# Helepolis_Level0.net
KiCad netlist of a schematic drawn in EAGLE
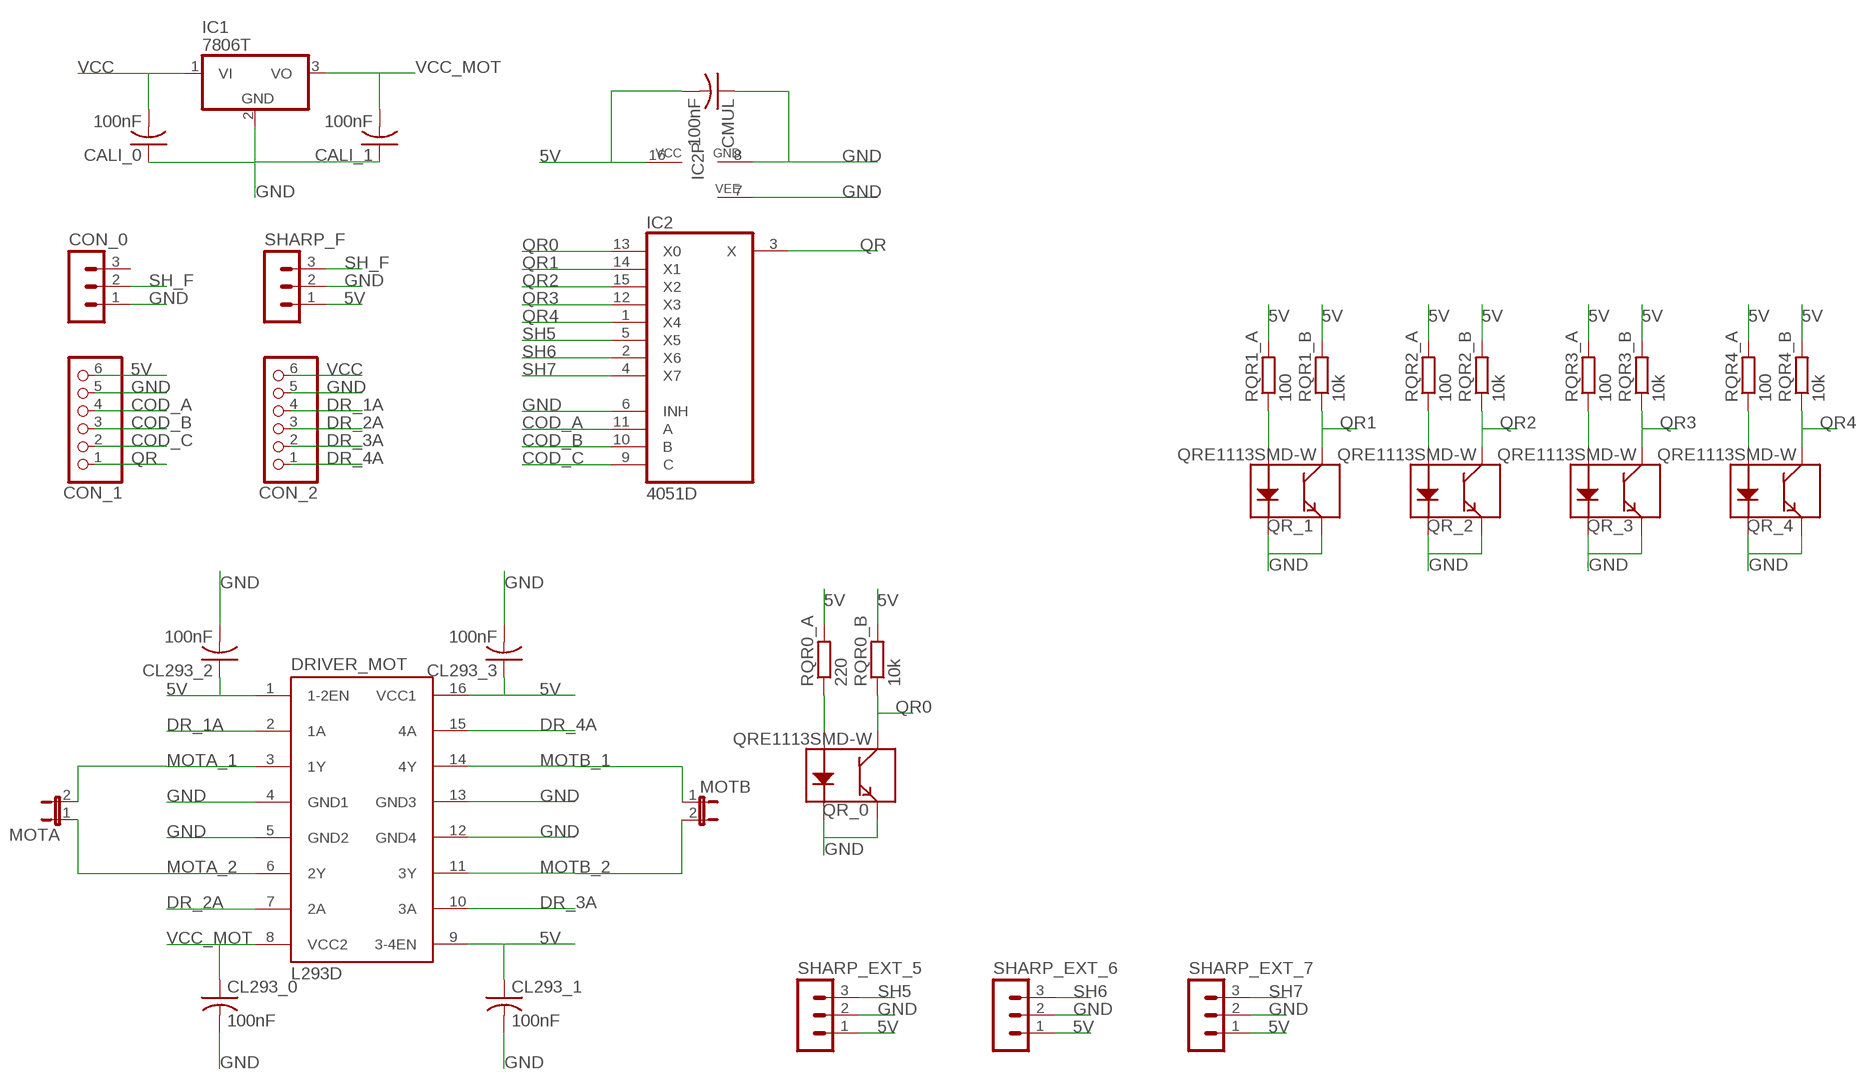
[diagram p0: schematic, sheet 1]

(export (version "E")
  (design (tool "Eeschema 10.0.6"))
  (components
    (comp (ref "CALI_0")
      (value "100nF")
      (footprint "eagle-import:C1206")
      (libsource (lib "eagle-import") (part "C-USC1206"))
    )
    (comp (ref "CALI_1")
      (value "100nF")
      (footprint "eagle-import:C1206")
      (libsource (lib "eagle-import") (part "C-USC1206"))
    )
    (comp (ref "CL293_0")
      (value "100nF")
      (footprint "eagle-import:C1206")
      (libsource (lib "eagle-import") (part "C-USC1206"))
    )
    (comp (ref "CL293_1")
      (value "100nF")
      (footprint "eagle-import:C1206")
      (libsource (lib "eagle-import") (part "C-USC1206"))
    )
    (comp (ref "CL293_2")
      (value "100nF")
      (footprint "eagle-import:C1206")
      (libsource (lib "eagle-import") (part "C-USC1206"))
    )
    (comp (ref "CL293_3")
      (value "100nF")
      (footprint "eagle-import:C1206")
      (libsource (lib "eagle-import") (part "C-USC1206"))
    )
    (comp (ref "CMUL")
      (value "100nF")
      (footprint "eagle-import:C1206")
      (libsource (lib "eagle-import") (part "C-USC1206"))
    )
    (comp (ref "CON_0")
      (value "MA03-1")
      (footprint "eagle-import:MA03-1")
      (libsource (lib "eagle-import") (part "MA03-1"))
    )
    (comp (ref "CON_1")
      (value "PINHD-1X6")
      (footprint "eagle-import:1X06")
      (libsource (lib "eagle-import") (part "PINHD-1X6"))
    )
    (comp (ref "CON_2")
      (value "PINHD-1X6")
      (footprint "eagle-import:1X06")
      (libsource (lib "eagle-import") (part "PINHD-1X6"))
    )
    (comp (ref "DRIVER_MOT")
      (value "L293D")
      (footprint "eagle-import:DIL16")
      (libsource (lib "eagle-import") (part "L293D"))
    )
    (comp (ref "IC1")
      (value "7806T")
      (footprint "eagle-import:TO220H")
      (libsource (lib "eagle-import") (part "78T06"))
    )
    (comp (ref "IC2")
      (value "4051D")
      (footprint "eagle-import:SO16")
      (libsource (lib "eagle-import") (part "4051D"))
    )
    (comp (ref "MOTA")
      (value "JP1E")
      (footprint "eagle-import:JP1")
      (libsource (lib "eagle-import") (part "JP1E"))
    )
    (comp (ref "MOTB")
      (value "JP1E")
      (footprint "eagle-import:JP1")
      (libsource (lib "eagle-import") (part "JP1E"))
    )
    (comp (ref "QR_0")
      (value "QRE1113SMD-W")
      (footprint "eagle-import:QRE1113-W")
      (libsource (lib "eagle-import") (part "QRE1113SMD-W"))
    )
    (comp (ref "QR_1")
      (value "QRE1113SMD-W")
      (footprint "eagle-import:QRE1113-W")
      (libsource (lib "eagle-import") (part "QRE1113SMD-W"))
    )
    (comp (ref "QR_2")
      (value "QRE1113SMD-W")
      (footprint "eagle-import:QRE1113-W")
      (libsource (lib "eagle-import") (part "QRE1113SMD-W"))
    )
    (comp (ref "QR_3")
      (value "QRE1113SMD-W")
      (footprint "eagle-import:QRE1113-W")
      (libsource (lib "eagle-import") (part "QRE1113SMD-W"))
    )
    (comp (ref "QR_4")
      (value "QRE1113SMD-W")
      (footprint "eagle-import:QRE1113-W")
      (libsource (lib "eagle-import") (part "QRE1113SMD-W"))
    )
    (comp (ref "RQR0_A")
      (value "220")
      (footprint "eagle-import:R1206")
      (libsource (lib "eagle-import") (part "R-EU_R1206"))
    )
    (comp (ref "RQR0_B")
      (value "10k")
      (footprint "eagle-import:R1206")
      (libsource (lib "eagle-import") (part "R-EU_R1206"))
    )
    (comp (ref "RQR1_A")
      (value "100")
      (footprint "eagle-import:R1206")
      (libsource (lib "eagle-import") (part "R-EU_R1206"))
    )
    (comp (ref "RQR1_B")
      (value "10k")
      (footprint "eagle-import:R1206")
      (libsource (lib "eagle-import") (part "R-EU_R1206"))
    )
    (comp (ref "RQR2_A")
      (value "100")
      (footprint "eagle-import:R1206")
      (libsource (lib "eagle-import") (part "R-EU_R1206"))
    )
    (comp (ref "RQR2_B")
      (value "10k")
      (footprint "eagle-import:R1206")
      (libsource (lib "eagle-import") (part "R-EU_R1206"))
    )
    (comp (ref "RQR3_A")
      (value "100")
      (footprint "eagle-import:R1206")
      (libsource (lib "eagle-import") (part "R-EU_R1206"))
    )
    (comp (ref "RQR3_B")
      (value "10k")
      (footprint "eagle-import:R1206")
      (libsource (lib "eagle-import") (part "R-EU_R1206"))
    )
    (comp (ref "RQR4_A")
      (value "100")
      (footprint "eagle-import:R1206")
      (libsource (lib "eagle-import") (part "R-EU_R1206"))
    )
    (comp (ref "RQR4_B")
      (value "10k")
      (footprint "eagle-import:R1206")
      (libsource (lib "eagle-import") (part "R-EU_R1206"))
    )
    (comp (ref "SHARP_EXT_5")
      (value "MA03-1")
      (footprint "eagle-import:MA03-1")
      (libsource (lib "eagle-import") (part "MA03-1"))
    )
    (comp (ref "SHARP_EXT_6")
      (value "MA03-1")
      (footprint "eagle-import:MA03-1")
      (libsource (lib "eagle-import") (part "MA03-1"))
    )
    (comp (ref "SHARP_EXT_7")
      (value "MA03-1")
      (footprint "eagle-import:MA03-1")
      (libsource (lib "eagle-import") (part "MA03-1"))
    )
    (comp (ref "SHARP_F")
      (value "MA03-1")
      (footprint "eagle-import:MA03-1")
      (libsource (lib "eagle-import") (part "MA03-1"))
    )
  )
  (nets
    (net (code "1") (name "/5V") (class "Default")
      (node (ref "CL293_1") (pin "1") (pinfunction "1_1") (pintype "passive"))
      (node (ref "CL293_2") (pin "1") (pinfunction "1_1") (pintype "passive"))
      (node (ref "CL293_3") (pin "1") (pinfunction "1_1") (pintype "passive"))
      (node (ref "CMUL") (pin "2") (pinfunction "2_2") (pintype "passive"))
      (node (ref "CON_1") (pin "6") (pinfunction "6_6") (pintype "passive"))
      (node (ref "DRIVER_MOT") (pin "1") (pinfunction "1-2EN_1") (pintype "input"))
      (node (ref "DRIVER_MOT") (pin "16") (pinfunction "VCC1_16") (pintype "power_in"))
      (node (ref "DRIVER_MOT") (pin "9") (pinfunction "3-4EN_9") (pintype "input"))
      (node (ref "IC2") (pin "16") (pinfunction "VCC_16") (pintype "power_in"))
      (node (ref "RQR0_A") (pin "2") (pinfunction "2_2") (pintype "passive"))
      (node (ref "RQR0_B") (pin "2") (pinfunction "2_2") (pintype "passive"))
      (node (ref "RQR1_A") (pin "2") (pinfunction "2_2") (pintype "passive"))
      (node (ref "RQR1_B") (pin "2") (pinfunction "2_2") (pintype "passive"))
      (node (ref "RQR2_A") (pin "2") (pinfunction "2_2") (pintype "passive"))
      (node (ref "RQR2_B") (pin "2") (pinfunction "2_2") (pintype "passive"))
      (node (ref "RQR3_A") (pin "2") (pinfunction "2_2") (pintype "passive"))
      (node (ref "RQR3_B") (pin "2") (pinfunction "2_2") (pintype "passive"))
      (node (ref "RQR4_A") (pin "2") (pinfunction "2_2") (pintype "passive"))
      (node (ref "RQR4_B") (pin "2") (pinfunction "2_2") (pintype "passive"))
      (node (ref "SHARP_EXT_5") (pin "1") (pinfunction "1_1") (pintype "passive"))
      (node (ref "SHARP_EXT_6") (pin "1") (pinfunction "1_1") (pintype "passive"))
      (node (ref "SHARP_EXT_7") (pin "1") (pinfunction "1_1") (pintype "passive"))
      (node (ref "SHARP_F") (pin "1") (pinfunction "1_1") (pintype "passive"))
    )
    (net (code "2") (name "/COD_A") (class "Default")
      (node (ref "CON_1") (pin "4") (pinfunction "4_4") (pintype "passive"))
      (node (ref "IC2") (pin "11") (pinfunction "A_11") (pintype "input"))
    )
    (net (code "3") (name "/COD_B") (class "Default")
      (node (ref "CON_1") (pin "3") (pinfunction "3_3") (pintype "passive"))
      (node (ref "IC2") (pin "10") (pinfunction "B_10") (pintype "input"))
    )
    (net (code "4") (name "/COD_C") (class "Default")
      (node (ref "CON_1") (pin "2") (pinfunction "2_2") (pintype "passive"))
      (node (ref "IC2") (pin "9") (pinfunction "C_9") (pintype "input"))
    )
    (net (code "5") (name "/DR_1A") (class "Default")
      (node (ref "CON_2") (pin "4") (pinfunction "4_4") (pintype "passive"))
      (node (ref "DRIVER_MOT") (pin "2") (pinfunction "1A_2") (pintype "input"))
    )
    (net (code "6") (name "/DR_2A") (class "Default")
      (node (ref "CON_2") (pin "3") (pinfunction "3_3") (pintype "passive"))
      (node (ref "DRIVER_MOT") (pin "7") (pinfunction "2A_7") (pintype "input"))
    )
    (net (code "7") (name "/DR_3A") (class "Default")
      (node (ref "CON_2") (pin "2") (pinfunction "2_2") (pintype "passive"))
      (node (ref "DRIVER_MOT") (pin "10") (pinfunction "3A_10") (pintype "input"))
    )
    (net (code "8") (name "/DR_4A") (class "Default")
      (node (ref "CON_2") (pin "1") (pinfunction "1_1") (pintype "passive"))
      (node (ref "DRIVER_MOT") (pin "15") (pinfunction "4A_15") (pintype "input"))
    )
    (net (code "9") (name "/GND") (class "Default")
      (node (ref "CALI_0") (pin "1") (pinfunction "1_1") (pintype "passive"))
      (node (ref "CALI_1") (pin "1") (pinfunction "1_1") (pintype "passive"))
      (node (ref "CL293_0") (pin "2") (pinfunction "2_2") (pintype "passive"))
      (node (ref "CL293_1") (pin "2") (pinfunction "2_2") (pintype "passive"))
      (node (ref "CL293_2") (pin "2") (pinfunction "2_2") (pintype "passive"))
      (node (ref "CL293_3") (pin "2") (pinfunction "2_2") (pintype "passive"))
      (node (ref "CMUL") (pin "1") (pinfunction "1_1") (pintype "passive"))
      (node (ref "CON_0") (pin "1") (pinfunction "1_1") (pintype "passive"))
      (node (ref "CON_1") (pin "5") (pinfunction "5_5") (pintype "passive"))
      (node (ref "CON_2") (pin "5") (pinfunction "5_5") (pintype "passive"))
      (node (ref "DRIVER_MOT") (pin "12") (pinfunction "GND4_12") (pintype "power_in"))
      (node (ref "DRIVER_MOT") (pin "13") (pinfunction "GND3_13") (pintype "power_in"))
      (node (ref "DRIVER_MOT") (pin "4") (pinfunction "GND1_4") (pintype "power_in"))
      (node (ref "DRIVER_MOT") (pin "5") (pinfunction "GND2_5") (pintype "power_in"))
      (node (ref "IC1") (pin "2") (pinfunction "GND_2") (pintype "passive"))
      (node (ref "IC2") (pin "6") (pinfunction "INH_6") (pintype "input"))
      (node (ref "IC2") (pin "7") (pinfunction "VEE_7") (pintype "power_in"))
      (node (ref "IC2") (pin "8") (pinfunction "GND_8") (pintype "power_in"))
      (node (ref "QR_0") (pin "2") (pinfunction "K_2") (pintype "bidirectional"))
      (node (ref "QR_0") (pin "4") (pinfunction "E_4") (pintype "bidirectional"))
      (node (ref "QR_1") (pin "2") (pinfunction "K_2") (pintype "bidirectional"))
      (node (ref "QR_1") (pin "4") (pinfunction "E_4") (pintype "bidirectional"))
      (node (ref "QR_2") (pin "2") (pinfunction "K_2") (pintype "bidirectional"))
      (node (ref "QR_2") (pin "4") (pinfunction "E_4") (pintype "bidirectional"))
      (node (ref "QR_3") (pin "2") (pinfunction "K_2") (pintype "bidirectional"))
      (node (ref "QR_3") (pin "4") (pinfunction "E_4") (pintype "bidirectional"))
      (node (ref "QR_4") (pin "2") (pinfunction "K_2") (pintype "bidirectional"))
      (node (ref "QR_4") (pin "4") (pinfunction "E_4") (pintype "bidirectional"))
      (node (ref "SHARP_EXT_5") (pin "2") (pinfunction "2_2") (pintype "passive"))
      (node (ref "SHARP_EXT_6") (pin "2") (pinfunction "2_2") (pintype "passive"))
      (node (ref "SHARP_EXT_7") (pin "2") (pinfunction "2_2") (pintype "passive"))
      (node (ref "SHARP_F") (pin "2") (pinfunction "2_2") (pintype "passive"))
    )
    (net (code "10") (name "/MOTA_1") (class "Default")
      (node (ref "DRIVER_MOT") (pin "3") (pinfunction "1Y_3") (pintype "output"))
      (node (ref "MOTA") (pin "2") (pinfunction "2_2") (pintype "passive"))
    )
    (net (code "11") (name "/MOTA_2") (class "Default")
      (node (ref "DRIVER_MOT") (pin "6") (pinfunction "2Y_6") (pintype "output"))
      (node (ref "MOTA") (pin "1") (pinfunction "1_1") (pintype "passive"))
    )
    (net (code "12") (name "/MOTB_1") (class "Default")
      (node (ref "DRIVER_MOT") (pin "14") (pinfunction "4Y_14") (pintype "output"))
      (node (ref "MOTB") (pin "1") (pinfunction "1_1") (pintype "passive"))
    )
    (net (code "13") (name "/MOTB_2") (class "Default")
      (node (ref "DRIVER_MOT") (pin "11") (pinfunction "3Y_11") (pintype "output"))
      (node (ref "MOTB") (pin "2") (pinfunction "2_2") (pintype "passive"))
    )
    (net (code "14") (name "/QR") (class "Default")
      (node (ref "CON_1") (pin "1") (pinfunction "1_1") (pintype "passive"))
      (node (ref "IC2") (pin "3") (pinfunction "X_3") (pintype "bidirectional"))
    )
    (net (code "15") (name "/QR0") (class "Default")
      (node (ref "IC2") (pin "13") (pinfunction "X0_13") (pintype "bidirectional"))
      (node (ref "QR_0") (pin "3") (pinfunction "C_3") (pintype "bidirectional"))
      (node (ref "RQR0_B") (pin "1") (pinfunction "1_1") (pintype "passive"))
    )
    (net (code "16") (name "/QR1") (class "Default")
      (node (ref "IC2") (pin "14") (pinfunction "X1_14") (pintype "bidirectional"))
      (node (ref "QR_1") (pin "3") (pinfunction "C_3") (pintype "bidirectional"))
      (node (ref "RQR1_B") (pin "1") (pinfunction "1_1") (pintype "passive"))
    )
    (net (code "17") (name "/QR2") (class "Default")
      (node (ref "IC2") (pin "15") (pinfunction "X2_15") (pintype "bidirectional"))
      (node (ref "QR_2") (pin "3") (pinfunction "C_3") (pintype "bidirectional"))
      (node (ref "RQR2_B") (pin "1") (pinfunction "1_1") (pintype "passive"))
    )
    (net (code "18") (name "/QR3") (class "Default")
      (node (ref "IC2") (pin "12") (pinfunction "X3_12") (pintype "bidirectional"))
      (node (ref "QR_3") (pin "3") (pinfunction "C_3") (pintype "bidirectional"))
      (node (ref "RQR3_B") (pin "1") (pinfunction "1_1") (pintype "passive"))
    )
    (net (code "19") (name "/QR4") (class "Default")
      (node (ref "IC2") (pin "1") (pinfunction "X4_1") (pintype "bidirectional"))
      (node (ref "QR_4") (pin "3") (pinfunction "C_3") (pintype "bidirectional"))
      (node (ref "RQR4_B") (pin "1") (pinfunction "1_1") (pintype "passive"))
    )
    (net (code "20") (name "/SH5") (class "Default")
      (node (ref "IC2") (pin "5") (pinfunction "X5_5") (pintype "bidirectional"))
      (node (ref "SHARP_EXT_5") (pin "3") (pinfunction "3_3") (pintype "passive"))
    )
    (net (code "21") (name "/SH6") (class "Default")
      (node (ref "IC2") (pin "2") (pinfunction "X6_2") (pintype "bidirectional"))
      (node (ref "SHARP_EXT_6") (pin "3") (pinfunction "3_3") (pintype "passive"))
    )
    (net (code "22") (name "/SH7") (class "Default")
      (node (ref "IC2") (pin "4") (pinfunction "X7_4") (pintype "bidirectional"))
      (node (ref "SHARP_EXT_7") (pin "3") (pinfunction "3_3") (pintype "passive"))
    )
    (net (code "23") (name "/SH_F") (class "Default")
      (node (ref "CON_0") (pin "2") (pinfunction "2_2") (pintype "passive"))
      (node (ref "SHARP_F") (pin "3") (pinfunction "3_3") (pintype "passive"))
    )
    (net (code "24") (name "/VCC") (class "Default")
      (node (ref "CALI_0") (pin "2") (pinfunction "2_2") (pintype "passive"))
      (node (ref "CON_2") (pin "6") (pinfunction "6_6") (pintype "passive"))
      (node (ref "IC1") (pin "1") (pinfunction "VI_1") (pintype "input"))
    )
    (net (code "25") (name "/VCC_MOT") (class "Default")
      (node (ref "CALI_1") (pin "2") (pinfunction "2_2") (pintype "passive"))
      (node (ref "CL293_0") (pin "1") (pinfunction "1_1") (pintype "passive"))
      (node (ref "DRIVER_MOT") (pin "8") (pinfunction "VCC2_8") (pintype "power_in"))
      (node (ref "IC1") (pin "3") (pinfunction "VO_3") (pintype "passive"))
    )
    (net (code "26") (name "Net-(QR_0-A)") (class "Default")
      (node (ref "QR_0") (pin "1") (pinfunction "A_1") (pintype "bidirectional"))
      (node (ref "RQR0_A") (pin "1") (pinfunction "1_1") (pintype "passive"))
    )
    (net (code "27") (name "Net-(QR_1-A)") (class "Default")
      (node (ref "QR_1") (pin "1") (pinfunction "A_1") (pintype "bidirectional"))
      (node (ref "RQR1_A") (pin "1") (pinfunction "1_1") (pintype "passive"))
    )
    (net (code "28") (name "Net-(QR_2-A)") (class "Default")
      (node (ref "QR_2") (pin "1") (pinfunction "A_1") (pintype "bidirectional"))
      (node (ref "RQR2_A") (pin "1") (pinfunction "1_1") (pintype "passive"))
    )
    (net (code "29") (name "Net-(QR_3-A)") (class "Default")
      (node (ref "QR_3") (pin "1") (pinfunction "A_1") (pintype "bidirectional"))
      (node (ref "RQR3_A") (pin "1") (pinfunction "1_1") (pintype "passive"))
    )
    (net (code "30") (name "Net-(QR_4-A)") (class "Default")
      (node (ref "QR_4") (pin "1") (pinfunction "A_1") (pintype "bidirectional"))
      (node (ref "RQR4_A") (pin "1") (pinfunction "1_1") (pintype "passive"))
    )
    (net (code "31") (name "unconnected-(CON_0-Pad3)") (class "Default")
      (node (ref "CON_0") (pin "3") (pinfunction "3_3") (pintype "passive"))
    )
  )
)
